# Li_ion_battery_charger-lceda.net
KiCad netlist of a schematic drawn in EasyEDA Pro
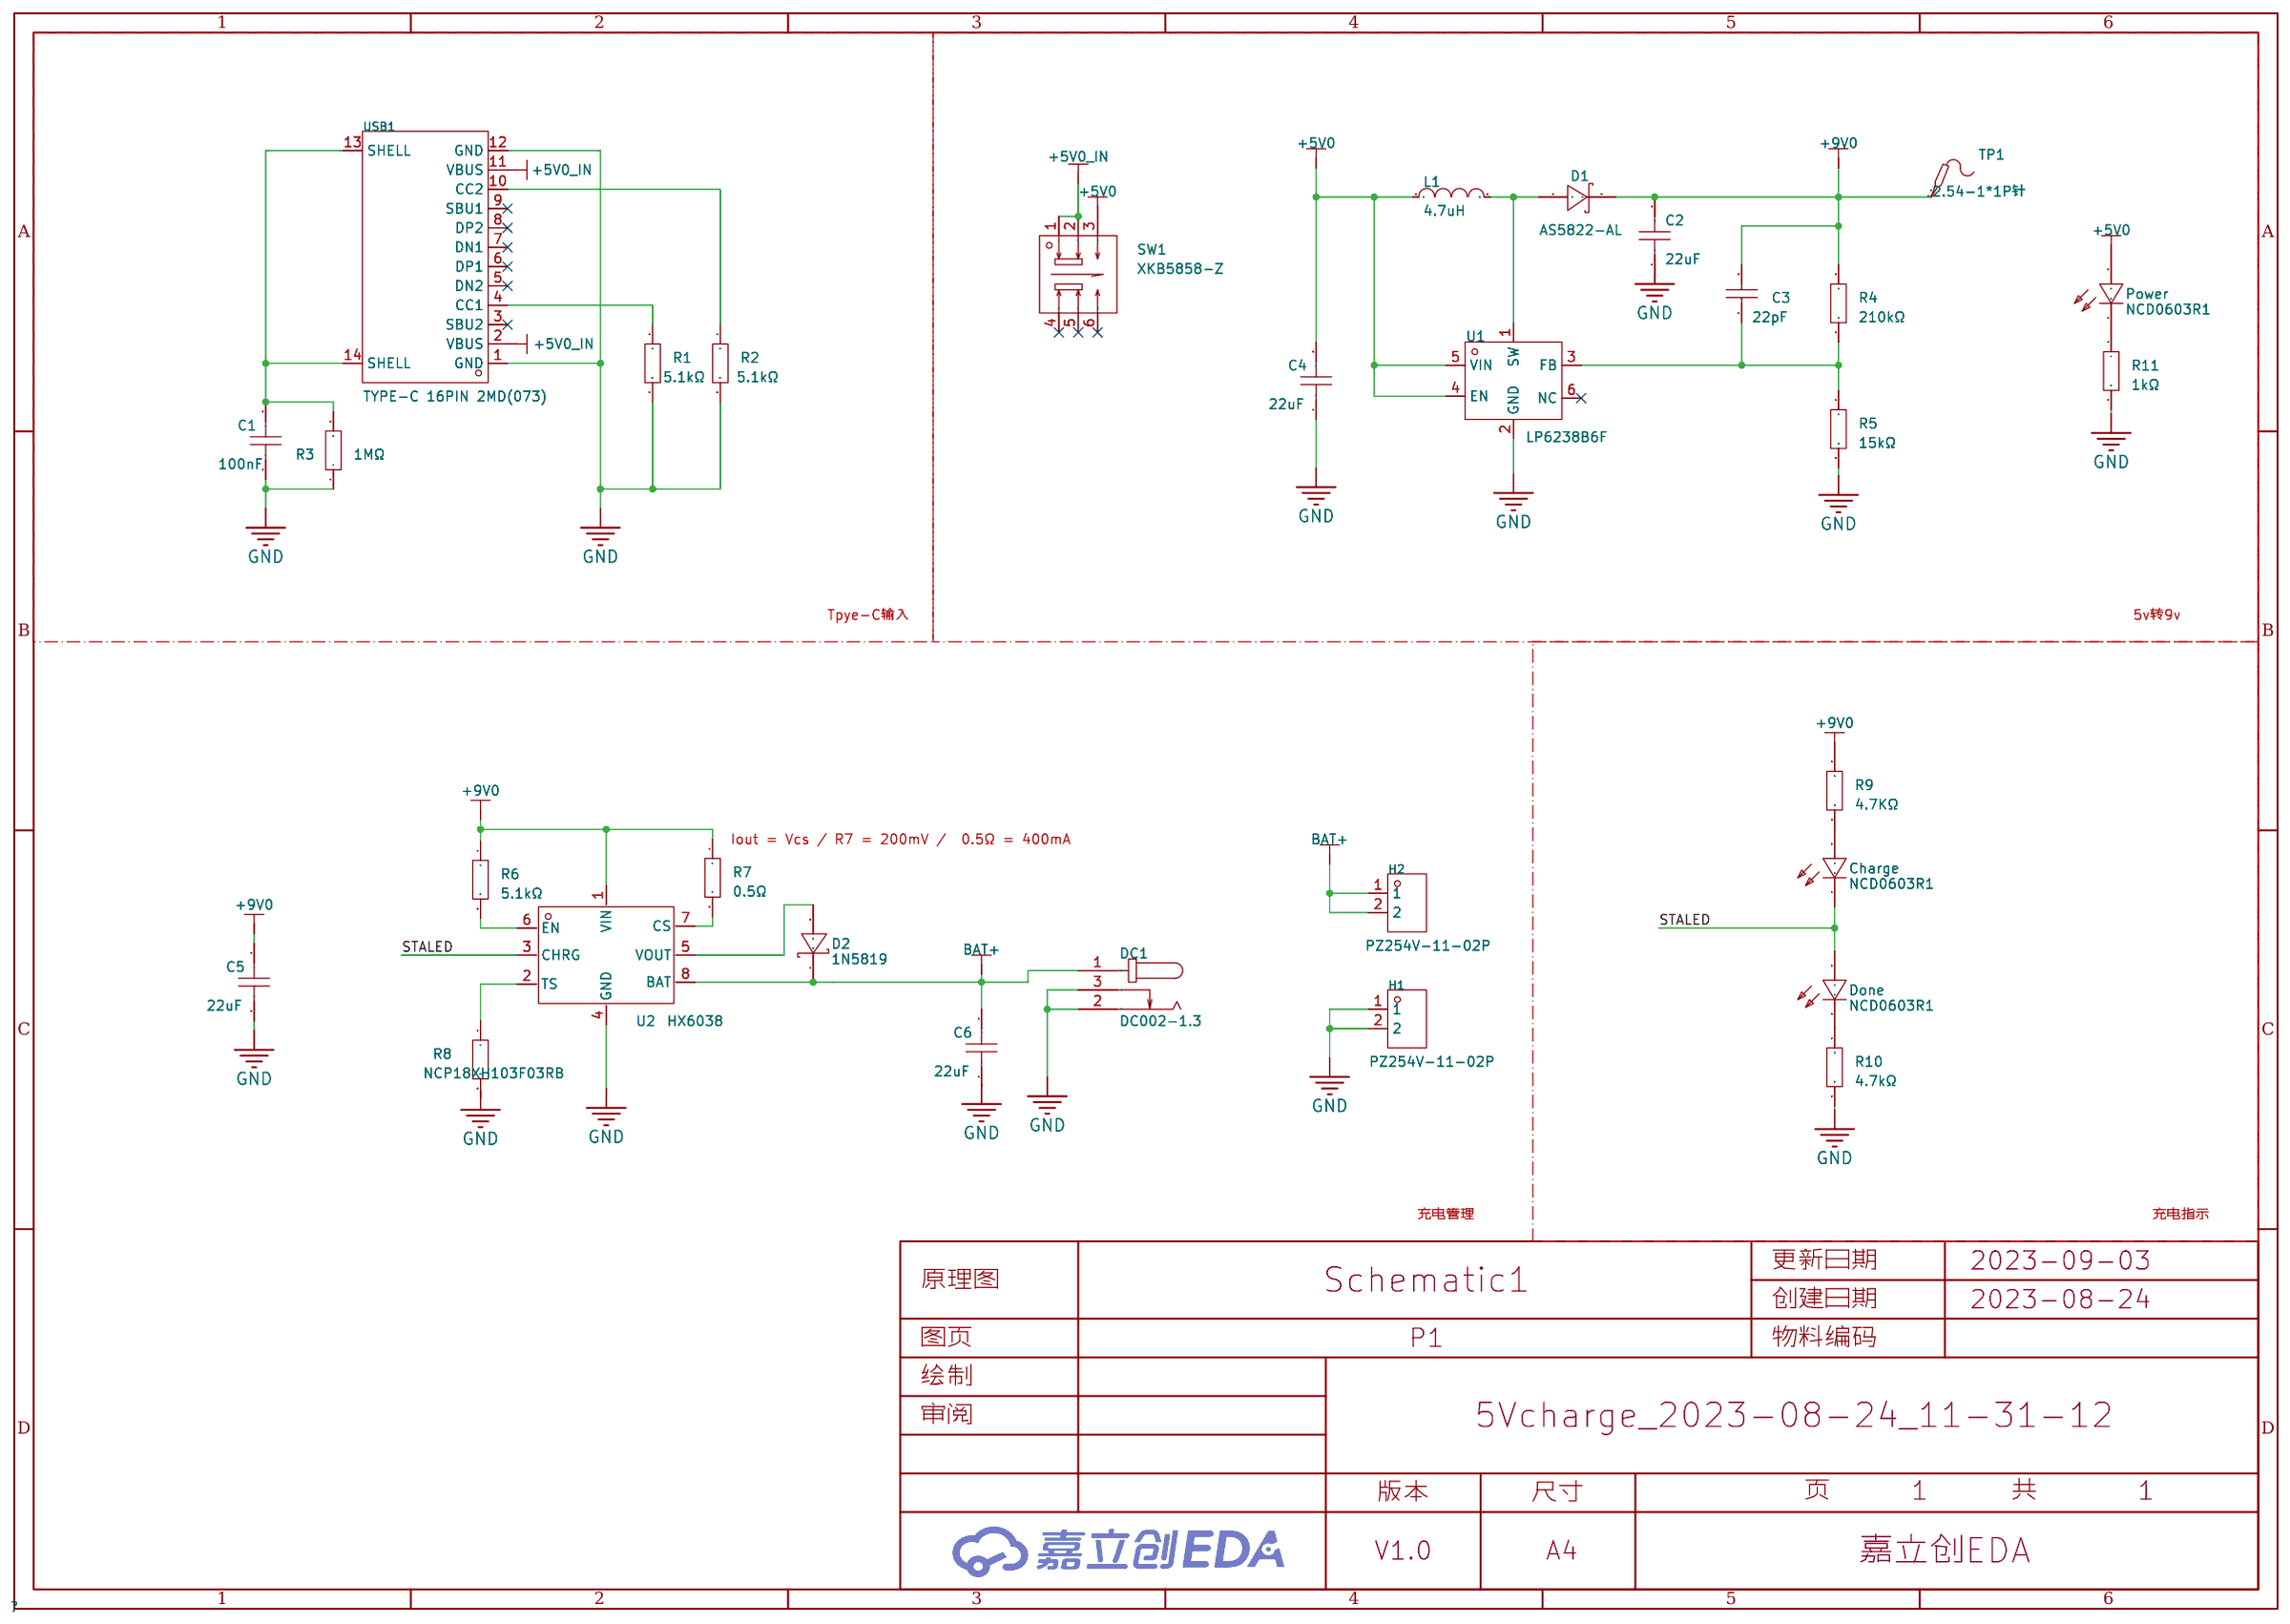
[diagram p0: schematic sheet]

(export (version "E")
  (design (tool "Eeschema 10.0.6"))
  (components
    (comp (ref "C1")
      (value "100nF")
      (footprint "easyedapro:C0603")
      (description "容值:100nF;精度:±10%;额定电压:50V;材质(温度系数):X7R;")
      (fields
        (field (name "Manufacturer Part") "CC0603KRX7R9BB104")
        (field (name "Manufacturer") "YAGEO(国巨)")
      )
      (libsource (lib "easyedapro") (part "CC0603KRX7R9BB104"))
    )
    (comp (ref "C2")
      (value "22uF")
      (footprint "easyedapro:C0603")
      (description "容值:100nF;精度:±10%;额定电压:50V;材质(温度系数):X7R;")
      (fields
        (field (name "Manufacturer Part") "CL31A226KAHNNNE")
        (field (name "Manufacturer") "SAMSUNG(三星)")
      )
      (libsource (lib "easyedapro") (part "CC0603KRX7R9BB104"))
    )
    (comp (ref "C3")
      (value "22pF")
      (footprint "easyedapro:C0603")
      (description "容值:22pF;精度:±5%;额定电压:50V;材质(温度系数):NP0;")
      (fields
        (field (name "Manufacturer Part") "CC0603JRNPO9BN220")
        (field (name "Manufacturer") "YAGEO(国巨)")
      )
      (libsource (lib "easyedapro") (part "CC0603JRNPO9BN220"))
    )
    (comp (ref "C4")
      (value "22uF")
      (footprint "easyedapro:C0603")
      (description "容值:100nF;精度:±10%;额定电压:50V;材质(温度系数):X7R;")
      (fields
        (field (name "Manufacturer Part") "CL31A226KAHNNNE")
        (field (name "Manufacturer") "SAMSUNG(三星)")
      )
      (libsource (lib "easyedapro") (part "CC0603KRX7R9BB104"))
    )
    (comp (ref "C5")
      (value "22uF")
      (footprint "easyedapro:C0603")
      (description "容值:100nF;精度:±10%;额定电压:50V;材质(温度系数):X7R;")
      (fields
        (field (name "Manufacturer Part") "CL31A226KAHNNNE")
        (field (name "Manufacturer") "SAMSUNG(三星)")
      )
      (libsource (lib "easyedapro") (part "CC0603KRX7R9BB104"))
    )
    (comp (ref "C6")
      (value "22uF")
      (footprint "easyedapro:C0603")
      (description "容值:100nF;精度:±10%;额定电压:50V;材质(温度系数):X7R;")
      (fields
        (field (name "Manufacturer Part") "CL31A226KAHNNNE")
        (field (name "Manufacturer") "SAMSUNG(三星)")
      )
      (libsource (lib "easyedapro") (part "CC0603KRX7R9BB104"))
    )
    (comp (ref "Charge")
      (value "NCD0603R1")
      (footprint "easyedapro:LED0603-RD_RED")
      (description "发光颜色:红灯;")
      (fields (field (name "Manufacturer") "国星光电"))
      (libsource (lib "easyedapro") (part "FC-DA1608HRK-620D"))
    )
    (comp (ref "D1")
      (value "AS5822-AL")
      (footprint "easyedapro:SMA-L_L4.4-W2.6-LS5.0-RD")
      (description "二极管配置:独立式;直流反向耐压(Vr):40V;平均整流电流(Io):3A;正向压降(Vf):500mV@3A;反向电流(Ir):500uA@40V;")
      (fields (field (name "Manufacturer") "AnBon(安邦)"))
      (libsource (lib "easyedapro") (part "AS5822-AL"))
    )
    (comp (ref "D2")
      (value "1N5819")
      (footprint "easyedapro:SMA_L4.4-W2.6-LS5.0-RD")
      (description "直流反向耐压(Vr):40V;平均整流电流(Io):1A;正向压降(Vf):500mV@1A;")
      (fields (field (name "Manufacturer") "KEXIN(科信)"))
      (libsource (lib "easyedapro") (part "1N5819_C437199"))
    )
    (comp (ref "DC1")
      (value "DC002-1.3")
      (footprint "easyedapro:DC-IN-TH_DC005")
      (description "连接器类型:DC电源插座;安装方式:弯插;触点内径:2mm;触点外径:6.3mm;额定电流:500mA;额定电压:30V;工作温度范围:-40℃~+55℃;")
      (fields (field (name "Manufacturer") "SHOU HAN(首韩)"))
      (libsource (lib "easyedapro") (part "DC005_C431533"))
    )
    (comp (ref "Done")
      (value "NCD0603R1")
      (footprint "easyedapro:LED0603-RD_RED")
      (description "发光颜色:红灯;")
      (fields (field (name "Manufacturer") "国星光电"))
      (libsource (lib "easyedapro") (part "FC-DA1608HRK-620D"))
    )
    (comp (ref "H1")
      (value "PZ254V-11-02P")
      (footprint "easyedapro:HDR-TH_2P-P2.54-V-M")
      (fields (field (name "Manufacturer") "XFCN(兴飞)"))
      (libsource (lib "easyedapro") (part "PZ254V-11-02P"))
    )
    (comp (ref "H2")
      (value "PZ254V-11-02P")
      (footprint "easyedapro:HDR-TH_2P-P2.54-V-M")
      (fields (field (name "Manufacturer") "XFCN(兴飞)"))
      (libsource (lib "easyedapro") (part "PZ254V-11-02P"))
    )
    (comp (ref "L1")
      (value "4.7uH")
      (footprint "easyedapro:IND-SMD_L4.0-W4.0")
      (description "直流电阻(DCR):78mΩ;精度:±20%;电感值:4.7uH;额定电流:2A;")
      (fields (field (name "Manufacturer Part") "SWPA4030S4R7MT") (field (name "Manufacturer") "Sunlord(顺络)"))
      (libsource (lib "easyedapro") (part "SWPA4030S4R7MT"))
    )
    (comp (ref "Power")
      (value "NCD0603R1")
      (footprint "easyedapro:LED0603-RD_RED")
      (description "发光颜色:红灯;")
      (fields (field (name "Manufacturer") "国星光电"))
      (libsource (lib "easyedapro") (part "FC-DA1608HRK-620D"))
    )
    (comp (ref "R1")
      (value "5.1kΩ")
      (footprint "easyedapro:R0603")
      (description "电阻类型:厚膜电阻;阻值:5.1kΩ;精度:±1%;功率:100mW;")
      (fields
        (field (name "Manufacturer Part") "0603WAF5101T5E")
        (field (name "Manufacturer") "UNI-ROYAL(厚声)")
      )
      (libsource (lib "easyedapro") (part "0603WAF5101T5E"))
    )
    (comp (ref "R2")
      (value "5.1kΩ")
      (footprint "easyedapro:R0603")
      (description "电阻类型:厚膜电阻;阻值:5.1kΩ;精度:±1%;功率:100mW;")
      (fields
        (field (name "Manufacturer Part") "0603WAF5101T5E")
        (field (name "Manufacturer") "UNI-ROYAL(厚声)")
      )
      (libsource (lib "easyedapro") (part "0603WAF5101T5E"))
    )
    (comp (ref "R3")
      (value "1MΩ")
      (footprint "easyedapro:R0603")
      (description "电阻类型:厚膜电阻;阻值:10kΩ;精度:±1%;功率:100mW;")
      (fields
        (field (name "Manufacturer Part") "0603WAF1002T5E")
        (field (name "Manufacturer") "UNI-ROYAL(厚声)")
      )
      (libsource (lib "easyedapro") (part "0603WAF1002T5E"))
    )
    (comp (ref "R4")
      (value "210kΩ")
      (footprint "easyedapro:R0603")
      (description "电阻类型:厚膜电阻;阻值:210kΩ;精度:±1%;功率:100mW;")
      (fields
        (field (name "Manufacturer Part") "0603WAF2103T5E")
        (field (name "Manufacturer") "UNI-ROYAL(厚声)")
      )
      (libsource (lib "easyedapro") (part "0603WAF2103T5E"))
    )
    (comp (ref "R5")
      (value "15kΩ")
      (footprint "easyedapro:R0603")
      (description "电阻类型:厚膜电阻;阻值:5.1kΩ;精度:±1%;功率:100mW;")
      (fields
        (field (name "Manufacturer Part") "0603WAF5101T5E")
        (field (name "Manufacturer") "UNI-ROYAL(厚声)")
      )
      (libsource (lib "easyedapro") (part "0603WAF5101T5E"))
    )
    (comp (ref "R6")
      (value "5.1kΩ")
      (footprint "easyedapro:R0603")
      (description "电阻类型:厚膜电阻;阻值:5.1kΩ;精度:±1%;功率:100mW;")
      (fields
        (field (name "Manufacturer Part") "0603WAF5101T5E")
        (field (name "Manufacturer") "UNI-ROYAL(厚声)")
      )
      (libsource (lib "easyedapro") (part "0603WAF5101T5E"))
    )
    (comp (ref "R7")
      (value "0.5Ω")
      (footprint "easyedapro:R0603")
      (description "电阻类型:厚膜电阻;阻值:5.1kΩ;精度:±1%;功率:100mW;")
      (fields
        (field (name "Manufacturer Part") "0603WAF5101T5E")
        (field (name "Manufacturer") "UNI-ROYAL(厚声)")
      )
      (libsource (lib "easyedapro") (part "0603WAF5101T5E"))
    )
    (comp (ref "R8")
      (value "10kΩ")
      (footprint "easyedapro:R0603")
      (description "电阻类型:厚膜电阻;阻值:5.1kΩ;精度:±1%;功率:100mW;")
      (fields (field (name "Manufacturer Part") "NCP18XH103F03RB") (field (name "Manufacturer") "muRata(村田)"))
      (libsource (lib "easyedapro") (part "0603WAF5101T5E"))
    )
    (comp (ref "R9")
      (value "4.7KΩ")
      (footprint "easyedapro:R0603")
      (description "电阻类型:厚膜电阻;阻值:5.1kΩ;精度:±1%;功率:100mW;")
      (fields
        (field (name "Manufacturer Part") "0603WAF5101T5E")
        (field (name "Manufacturer") "UNI-ROYAL(厚声)")
      )
      (libsource (lib "easyedapro") (part "0603WAF5101T5E"))
    )
    (comp (ref "R10")
      (value "4.7kΩ")
      (footprint "easyedapro:R0603")
      (description "电阻类型:厚膜电阻;阻值:5.1kΩ;精度:±1%;功率:100mW;")
      (fields
        (field (name "Manufacturer Part") "0603WAF5101T5E")
        (field (name "Manufacturer") "UNI-ROYAL(厚声)")
      )
      (libsource (lib "easyedapro") (part "0603WAF5101T5E"))
    )
    (comp (ref "R11")
      (value "1kΩ")
      (footprint "easyedapro:R0603")
      (description "电阻类型:厚膜电阻;阻值:5.1kΩ;精度:±1%;功率:100mW;")
      (fields
        (field (name "Manufacturer Part") "0603WAF5101T5E")
        (field (name "Manufacturer") "UNI-ROYAL(厚声)")
      )
      (libsource (lib "easyedapro") (part "0603WAF5101T5E"))
    )
    (comp (ref "SW1")
      (value "XKB5858-Z")
      (footprint "easyedapro:SW-TH_6P-L5.8-W5.8-P2.00-LS4.5-BL")
      (fields (field (name "Manufacturer") "XKB Connectivity(中国星坤)"))
      (libsource (lib "easyedapro") (part "XKB5858-Z"))
    )
    (comp (ref "TP1")
      (value "2.54-1*1P针")
      (footprint "easyedapro:Test-Point-0.5mm")
      (description "Test Point 测试点")
      (fields (field (name "Manufacturer") "BOOMELE(博穆精密)"))
      (libsource (lib "easyedapro") (part "Test-Point"))
    )
    (comp (ref "U1")
      (value "LP6238B6F")
      (footprint "easyedapro:SOT-23-6_L2.9-W1.6-P0.95-LS2.8-BL")
      (description "2.6A MOS电流")
      (fields (field (name "Manufacturer") "LOWPOWER(微源半导体)"))
      (libsource (lib "easyedapro") (part "LP6238B6F"))
    )
    (comp (ref "U2")
      (value "HX6038")
      (footprint "easyedapro:ESOP-8_L4.9-W3.9-P1.27-LS6.0-BL-EP")
      (fields (field (name "Manufacturer") "INJOINIC(英集芯)"))
      (libsource (lib "easyedapro") (part "IP2312U"))
    )
    (comp (ref "USB1")
      (value "TYPE-C 16PIN 2MD(073)")
      (footprint "easyedapro:USB-C-SMD_TYPE-C-6PIN-2MD-073")
      (description "连接器类型:Type-C;标准:-;公母:母座;触点数量:16;端口数量:1;安装方式:卧贴;额定电流 - 电源:5A;工作温度范围:-25°C~+85°C;")
      (fields (field (name "Manufacturer") "SHOU HAN(首韩)"))
      (libsource (lib "easyedapro") (part "TYPE-C 16PIN 2MD(073)"))
    )
  )
  (nets
    (net (code "1") (name "+5V0") (class "Default")
      (node (ref "C4") (pin "2") (pinfunction "2_2") (pintype "input"))
      (node (ref "L1") (pin "1") (pinfunction "1_1") (pintype "input"))
      (node (ref "Power") (pin "2") (pinfunction "A_2") (pintype "input"))
      (node (ref "SW1") (pin "3") (pinfunction "3_3") (pintype "input"))
      (node (ref "U1") (pin "4") (pinfunction "EN_4") (pintype "input"))
      (node (ref "U1") (pin "5") (pinfunction "VIN_5") (pintype "input"))
    )
    (net (code "2") (name "+5V0_IN") (class "Default")
      (node (ref "SW1") (pin "1") (pinfunction "1_1") (pintype "input"))
      (node (ref "SW1") (pin "2") (pinfunction "2_2") (pintype "input"))
      (node (ref "USB1") (pin "11") (pinfunction "VBUS_11") (pintype "input"))
      (node (ref "USB1") (pin "2") (pinfunction "VBUS_2") (pintype "input"))
    )
    (net (code "3") (name "+9V0") (class "Default")
      (node (ref "C2") (pin "2") (pinfunction "2_2") (pintype "input"))
      (node (ref "C3") (pin "2") (pinfunction "2_2") (pintype "input"))
      (node (ref "C5") (pin "2") (pinfunction "2_2") (pintype "input"))
      (node (ref "D1") (pin "1") (pinfunction "A_1") (pintype "input"))
      (node (ref "R4") (pin "2") (pinfunction "2_2") (pintype "input"))
      (node (ref "R6") (pin "1") (pinfunction "1_1") (pintype "input"))
      (node (ref "R7") (pin "1") (pinfunction "1_1") (pintype "input"))
      (node (ref "R9") (pin "1") (pinfunction "1_1") (pintype "input"))
      (node (ref "TP1") (pin "1") (pinfunction "1_1") (pintype "input"))
      (node (ref "U2") (pin "1") (pinfunction "VIN_1") (pintype "input"))
    )
    (net (code "4") (name "/STALED") (class "Default")
      (node (ref "Charge") (pin "1") (pinfunction "K_1") (pintype "input"))
      (node (ref "Done") (pin "2") (pinfunction "A_2") (pintype "input"))
      (node (ref "U2") (pin "3") (pinfunction "CHRG_3") (pintype "input"))
    )
    (net (code "5") (name "BAT+") (class "Default")
      (node (ref "C6") (pin "2") (pinfunction "2_2") (pintype "input"))
      (node (ref "D2") (pin "1") (pinfunction "C_1") (pintype "input"))
      (node (ref "DC1") (pin "1") (pinfunction "1_1") (pintype "input"))
      (node (ref "H2") (pin "1") (pinfunction "1_1") (pintype "input"))
      (node (ref "H2") (pin "2") (pinfunction "2_2") (pintype "input"))
      (node (ref "U2") (pin "8") (pinfunction "BAT_8") (pintype "input"))
    )
    (net (code "6") (name "GND") (class "Default")
      (node (ref "C1") (pin "1") (pinfunction "1_1") (pintype "input"))
      (node (ref "C2") (pin "1") (pinfunction "1_1") (pintype "input"))
      (node (ref "C4") (pin "1") (pinfunction "1_1") (pintype "input"))
      (node (ref "C5") (pin "1") (pinfunction "1_1") (pintype "input"))
      (node (ref "C6") (pin "1") (pinfunction "1_1") (pintype "input"))
      (node (ref "DC1") (pin "2") (pinfunction "2_2") (pintype "input"))
      (node (ref "DC1") (pin "3") (pinfunction "3_3") (pintype "input"))
      (node (ref "H1") (pin "1") (pinfunction "1_1") (pintype "input"))
      (node (ref "H1") (pin "2") (pinfunction "2_2") (pintype "input"))
      (node (ref "R1") (pin "2") (pinfunction "2_2") (pintype "input"))
      (node (ref "R10") (pin "2") (pinfunction "2_2") (pintype "input"))
      (node (ref "R11") (pin "2") (pinfunction "2_2") (pintype "input"))
      (node (ref "R2") (pin "2") (pinfunction "2_2") (pintype "input"))
      (node (ref "R3") (pin "1") (pinfunction "1_1") (pintype "input"))
      (node (ref "R5") (pin "2") (pinfunction "2_2") (pintype "input"))
      (node (ref "R8") (pin "2") (pinfunction "2_2") (pintype "input"))
      (node (ref "U1") (pin "2") (pinfunction "GND_2") (pintype "input"))
      (node (ref "U2") (pin "4") (pinfunction "GND_4") (pintype "input"))
      (node (ref "USB1") (pin "1") (pinfunction "GND_1") (pintype "input"))
      (node (ref "USB1") (pin "12") (pinfunction "GND_12") (pintype "input"))
    )
    (net (code "7") (name "Net-(C1-Pad2)") (class "Default")
      (node (ref "C1") (pin "2") (pinfunction "2_2") (pintype "input"))
      (node (ref "R3") (pin "2") (pinfunction "2_2") (pintype "input"))
      (node (ref "USB1") (pin "13") (pinfunction "SHELL_13") (pintype "input"))
      (node (ref "USB1") (pin "14") (pinfunction "SHELL_14") (pintype "input"))
    )
    (net (code "8") (name "Net-(Charge-A)") (class "Default")
      (node (ref "Charge") (pin "2") (pinfunction "A_2") (pintype "input"))
      (node (ref "R9") (pin "2") (pinfunction "2_2") (pintype "input"))
    )
    (net (code "9") (name "Net-(D1-K)") (class "Default")
      (node (ref "D1") (pin "2") (pinfunction "K_2") (pintype "input"))
      (node (ref "L1") (pin "2") (pinfunction "2_2") (pintype "input"))
      (node (ref "U1") (pin "1") (pinfunction "SW_1") (pintype "input"))
    )
    (net (code "10") (name "Net-(D2-A)") (class "Default")
      (node (ref "D2") (pin "2") (pinfunction "A_2") (pintype "input"))
      (node (ref "U2") (pin "5") (pinfunction "VOUT_5") (pintype "input"))
    )
    (net (code "11") (name "Net-(Done-K)") (class "Default")
      (node (ref "Done") (pin "1") (pinfunction "K_1") (pintype "input"))
      (node (ref "R10") (pin "1") (pinfunction "1_1") (pintype "input"))
    )
    (net (code "12") (name "Net-(Power-K)") (class "Default")
      (node (ref "Power") (pin "1") (pinfunction "K_1") (pintype "input"))
      (node (ref "R11") (pin "1") (pinfunction "1_1") (pintype "input"))
    )
    (net (code "13") (name "Net-(U1-FB)") (class "Default")
      (node (ref "C3") (pin "1") (pinfunction "1_1") (pintype "input"))
      (node (ref "R4") (pin "1") (pinfunction "1_1") (pintype "input"))
      (node (ref "R5") (pin "1") (pinfunction "1_1") (pintype "input"))
      (node (ref "U1") (pin "3") (pinfunction "FB_3") (pintype "input"))
    )
    (net (code "14") (name "Net-(U2-CS)") (class "Default")
      (node (ref "R7") (pin "2") (pinfunction "2_2") (pintype "input"))
      (node (ref "U2") (pin "7") (pinfunction "CS_7") (pintype "input"))
    )
    (net (code "15") (name "Net-(U2-EN)") (class "Default")
      (node (ref "R6") (pin "2") (pinfunction "2_2") (pintype "input"))
      (node (ref "U2") (pin "6") (pinfunction "EN_6") (pintype "input"))
    )
    (net (code "16") (name "Net-(U2-TS)") (class "Default")
      (node (ref "R8") (pin "1") (pinfunction "1_1") (pintype "input"))
      (node (ref "U2") (pin "2") (pinfunction "TS_2") (pintype "input"))
    )
    (net (code "17") (name "Net-(USB1-CC1)") (class "Default")
      (node (ref "R1") (pin "1") (pinfunction "1_1") (pintype "input"))
      (node (ref "USB1") (pin "4") (pinfunction "CC1_4") (pintype "input"))
    )
    (net (code "18") (name "Net-(USB1-CC2)") (class "Default")
      (node (ref "R2") (pin "1") (pinfunction "1_1") (pintype "input"))
      (node (ref "USB1") (pin "10") (pinfunction "CC2_10") (pintype "input"))
    )
    (net (code "19") (name "unconnected-(SW1-Pad4)") (class "Default")
      (node (ref "SW1") (pin "4") (pinfunction "4_4") (pintype "input+no_connect"))
    )
    (net (code "20") (name "unconnected-(SW1-Pad5)") (class "Default")
      (node (ref "SW1") (pin "5") (pinfunction "5_5") (pintype "input+no_connect"))
    )
    (net (code "21") (name "unconnected-(SW1-Pad6)") (class "Default")
      (node (ref "SW1") (pin "6") (pinfunction "6_6") (pintype "input+no_connect"))
    )
    (net (code "22") (name "unconnected-(U1-NC-Pad6)") (class "Default")
      (node (ref "U1") (pin "6") (pinfunction "NC_6") (pintype "input+no_connect"))
    )
    (net (code "23") (name "unconnected-(USB1-DN1-Pad7)") (class "Default")
      (node (ref "USB1") (pin "7") (pinfunction "DN1_7") (pintype "input+no_connect"))
    )
    (net (code "24") (name "unconnected-(USB1-DN2-Pad5)") (class "Default")
      (node (ref "USB1") (pin "5") (pinfunction "DN2_5") (pintype "input+no_connect"))
    )
    (net (code "25") (name "unconnected-(USB1-DP1-Pad6)") (class "Default")
      (node (ref "USB1") (pin "6") (pinfunction "DP1_6") (pintype "input+no_connect"))
    )
    (net (code "26") (name "unconnected-(USB1-DP2-Pad8)") (class "Default")
      (node (ref "USB1") (pin "8") (pinfunction "DP2_8") (pintype "input+no_connect"))
    )
    (net (code "27") (name "unconnected-(USB1-SBU1-Pad9)") (class "Default")
      (node (ref "USB1") (pin "9") (pinfunction "SBU1_9") (pintype "input+no_connect"))
    )
    (net (code "28") (name "unconnected-(USB1-SBU2-Pad3)") (class "Default")
      (node (ref "USB1") (pin "3") (pinfunction "SBU2_3") (pintype "input+no_connect"))
    )
  )
)
